# MFP_PCB_2layer_v2.net
KiCad netlist of a schematic drawn in EAGLE
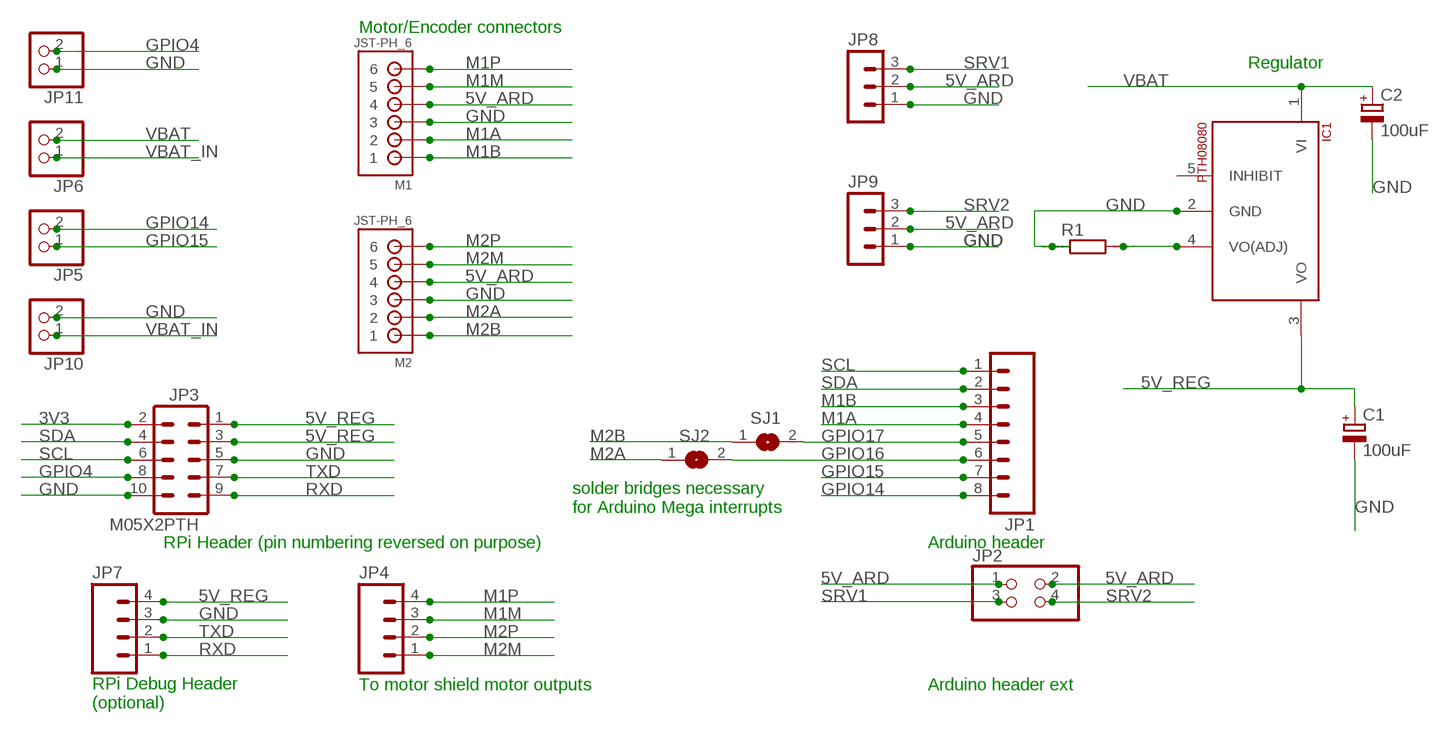
[diagram p0: schematic, sheet 1]

(export (version "E")
  (design (tool "Eeschema 10.0.6"))
  (components
    (comp (ref "C1")
      (value "100uF")
      (footprint "eagle-import:150CLZ-0810")
      (libsource (lib "eagle-import") (part "CPOL-EU150CLZ-0810"))
    )
    (comp (ref "C2")
      (value "100uF")
      (footprint "eagle-import:150CLZ-0810")
      (libsource (lib "eagle-import") (part "CPOL-EU150CLZ-0810"))
    )
    (comp (ref "IC1")
      (value "PTH08080")
      (footprint "eagle-import:PTH08080")
      (libsource (lib "eagle-import") (part "PTH08080"))
    )
    (comp (ref "JP1")
      (value "M08LONGPADS")
      (footprint "eagle-import:1X08_LONGPADS")
      (libsource (lib "eagle-import") (part "M08LONGPADS"))
    )
    (comp (ref "JP2")
      (value "PINHD-2X2")
      (footprint "eagle-import:2X02")
      (libsource (lib "eagle-import") (part "PINHD-2X2"))
    )
    (comp (ref "JP3")
      (value "M05X2PTH")
      (footprint "eagle-import:AVR_ICSP")
      (libsource (lib "eagle-import") (part "M05X2PTH"))
    )
    (comp (ref "JP4")
      (value "M04PTH")
      (footprint "eagle-import:1X04")
      (libsource (lib "eagle-import") (part "M04PTH"))
    )
    (comp (ref "JP5")
      (value "PINHD-1X2")
      (footprint "eagle-import:1X02")
      (libsource (lib "eagle-import") (part "PINHD-1X2"))
    )
    (comp (ref "JP6")
      (value "PINHD-1X2")
      (footprint "eagle-import:1X02")
      (libsource (lib "eagle-import") (part "PINHD-1X2"))
    )
    (comp (ref "JP7")
      (value "M04PTH")
      (footprint "eagle-import:1X04")
      (libsource (lib "eagle-import") (part "M04PTH"))
    )
    (comp (ref "JP8")
      (value "MA03-1")
      (footprint "eagle-import:MA03-1")
      (libsource (lib "eagle-import") (part "MA03-1"))
    )
    (comp (ref "JP9")
      (value "MA03-1")
      (footprint "eagle-import:MA03-1")
      (libsource (lib "eagle-import") (part "MA03-1"))
    )
    (comp (ref "JP10")
      (value "PINHD-1X2")
      (footprint "eagle-import:1X02")
      (libsource (lib "eagle-import") (part "PINHD-1X2"))
    )
    (comp (ref "JP11")
      (value "PINHD-1X2")
      (footprint "eagle-import:1X02")
      (libsource (lib "eagle-import") (part "PINHD-1X2"))
    )
    (comp (ref "M1")
      (value "JST-PH_6")
      (footprint "eagle-import:JST_B6B-PH_HEADER")
      (libsource (lib "eagle-import") (part "JST-PH_6"))
    )
    (comp (ref "M2")
      (value "JST-PH_6")
      (footprint "eagle-import:JST_B6B-PH_HEADER")
      (libsource (lib "eagle-import") (part "JST-PH_6"))
    )
    (comp (ref "R1")
      (value "R0204/7")
      (footprint "eagle-import:0204_7")
      (libsource (lib "eagle-import") (part "R0204/7"))
    )
    (comp (ref "SJ1") (value "SJ") (footprint "eagle-import:SJ") (libsource (lib "eagle-import") (part "SJ")))
    (comp (ref "SJ2") (value "SJ") (footprint "eagle-import:SJ") (libsource (lib "eagle-import") (part "SJ")))
  )
  (nets
    (net (code "1") (name "/3V3") (class "Default")
      (node (ref "JP3") (pin "2") (pinfunction "2_2") (pintype "passive"))
    )
    (net (code "2") (name "/5V_ARD") (class "Default")
      (node (ref "JP2") (pin "1") (pinfunction "1_1") (pintype "passive"))
      (node (ref "JP2") (pin "2") (pinfunction "2_2") (pintype "passive"))
      (node (ref "JP8") (pin "2") (pinfunction "2_2") (pintype "passive"))
      (node (ref "JP9") (pin "2") (pinfunction "2_2") (pintype "passive"))
      (node (ref "M1") (pin "P4") (pinfunction "4_P4") (pintype "bidirectional"))
      (node (ref "M2") (pin "P4") (pinfunction "4_P4") (pintype "bidirectional"))
    )
    (net (code "3") (name "/5V_REG") (class "Default")
      (node (ref "C1") (pin "+") (pinfunction "+_+") (pintype "passive"))
      (node (ref "IC1") (pin "3") (pinfunction "VO_3") (pintype "bidirectional"))
      (node (ref "JP3") (pin "1") (pinfunction "1_1") (pintype "passive"))
      (node (ref "JP3") (pin "3") (pinfunction "3_3") (pintype "passive"))
      (node (ref "JP7") (pin "4") (pinfunction "4_4") (pintype "passive"))
    )
    (net (code "4") (name "/GND") (class "Default")
      (node (ref "C1") (pin "-") (pinfunction "-_-") (pintype "passive"))
      (node (ref "C2") (pin "-") (pinfunction "-_-") (pintype "passive"))
      (node (ref "IC1") (pin "2") (pinfunction "GND_2") (pintype "bidirectional"))
      (node (ref "JP10") (pin "2") (pinfunction "2_2") (pintype "passive"))
      (node (ref "JP11") (pin "1") (pinfunction "1_1") (pintype "passive"))
      (node (ref "JP3") (pin "10") (pinfunction "10_10") (pintype "passive"))
      (node (ref "JP3") (pin "5") (pinfunction "5_5") (pintype "passive"))
      (node (ref "JP7") (pin "3") (pinfunction "3_3") (pintype "passive"))
      (node (ref "JP8") (pin "1") (pinfunction "1_1") (pintype "passive"))
      (node (ref "JP9") (pin "1") (pinfunction "1_1") (pintype "passive"))
      (node (ref "M1") (pin "P3") (pinfunction "3_P3") (pintype "bidirectional"))
      (node (ref "M2") (pin "P3") (pinfunction "3_P3") (pintype "bidirectional"))
      (node (ref "R1") (pin "1") (pinfunction "1_1") (pintype "passive"))
    )
    (net (code "5") (name "/GPIO4") (class "Default")
      (node (ref "JP11") (pin "2") (pinfunction "2_2") (pintype "passive"))
      (node (ref "JP3") (pin "8") (pinfunction "8_8") (pintype "passive"))
    )
    (net (code "6") (name "/GPIO14") (class "Default")
      (node (ref "JP1") (pin "8") (pinfunction "8_8") (pintype "passive"))
      (node (ref "JP5") (pin "2") (pinfunction "2_2") (pintype "passive"))
    )
    (net (code "7") (name "/GPIO15") (class "Default")
      (node (ref "JP1") (pin "7") (pinfunction "7_7") (pintype "passive"))
      (node (ref "JP5") (pin "1") (pinfunction "1_1") (pintype "passive"))
    )
    (net (code "8") (name "/GPIO16") (class "Default")
      (node (ref "JP1") (pin "6") (pinfunction "6_6") (pintype "passive"))
      (node (ref "SJ2") (pin "2") (pinfunction "2_2") (pintype "passive"))
    )
    (net (code "9") (name "/GPIO17") (class "Default")
      (node (ref "JP1") (pin "5") (pinfunction "5_5") (pintype "passive"))
      (node (ref "SJ1") (pin "2") (pinfunction "2_2") (pintype "passive"))
    )
    (net (code "10") (name "/M1A") (class "Default")
      (node (ref "JP1") (pin "4") (pinfunction "4_4") (pintype "passive"))
      (node (ref "M1") (pin "P2") (pinfunction "2_P2") (pintype "bidirectional"))
    )
    (net (code "11") (name "/M1B") (class "Default")
      (node (ref "JP1") (pin "3") (pinfunction "3_3") (pintype "passive"))
      (node (ref "M1") (pin "P1") (pinfunction "1_P1") (pintype "bidirectional"))
    )
    (net (code "12") (name "/M1M") (class "Default")
      (node (ref "JP4") (pin "3") (pinfunction "3_3") (pintype "passive"))
      (node (ref "M1") (pin "P5") (pinfunction "5_P5") (pintype "bidirectional"))
    )
    (net (code "13") (name "/M1P") (class "Default")
      (node (ref "JP4") (pin "4") (pinfunction "4_4") (pintype "passive"))
      (node (ref "M1") (pin "P6") (pinfunction "6_P6") (pintype "bidirectional"))
    )
    (net (code "14") (name "/M2A") (class "Default")
      (node (ref "M2") (pin "P2") (pinfunction "2_P2") (pintype "bidirectional"))
      (node (ref "SJ2") (pin "1") (pinfunction "1_1") (pintype "passive"))
    )
    (net (code "15") (name "/M2B") (class "Default")
      (node (ref "M2") (pin "P1") (pinfunction "1_P1") (pintype "bidirectional"))
      (node (ref "SJ1") (pin "1") (pinfunction "1_1") (pintype "passive"))
    )
    (net (code "16") (name "/M2M") (class "Default")
      (node (ref "JP4") (pin "1") (pinfunction "1_1") (pintype "passive"))
      (node (ref "M2") (pin "P5") (pinfunction "5_P5") (pintype "bidirectional"))
    )
    (net (code "17") (name "/M2P") (class "Default")
      (node (ref "JP4") (pin "2") (pinfunction "2_2") (pintype "passive"))
      (node (ref "M2") (pin "P6") (pinfunction "6_P6") (pintype "bidirectional"))
    )
    (net (code "18") (name "/RXD") (class "Default")
      (node (ref "JP3") (pin "9") (pinfunction "9_9") (pintype "passive"))
      (node (ref "JP7") (pin "1") (pinfunction "1_1") (pintype "passive"))
    )
    (net (code "19") (name "/SCL") (class "Default")
      (node (ref "JP1") (pin "1") (pinfunction "1_1") (pintype "passive"))
      (node (ref "JP3") (pin "6") (pinfunction "6_6") (pintype "passive"))
    )
    (net (code "20") (name "/SDA") (class "Default")
      (node (ref "JP1") (pin "2") (pinfunction "2_2") (pintype "passive"))
      (node (ref "JP3") (pin "4") (pinfunction "4_4") (pintype "passive"))
    )
    (net (code "21") (name "/SRV1") (class "Default")
      (node (ref "JP2") (pin "3") (pinfunction "3_3") (pintype "passive"))
      (node (ref "JP8") (pin "3") (pinfunction "3_3") (pintype "passive"))
    )
    (net (code "22") (name "/SRV2") (class "Default")
      (node (ref "JP2") (pin "4") (pinfunction "4_4") (pintype "passive"))
      (node (ref "JP9") (pin "3") (pinfunction "3_3") (pintype "passive"))
    )
    (net (code "23") (name "/TXD") (class "Default")
      (node (ref "JP3") (pin "7") (pinfunction "7_7") (pintype "passive"))
      (node (ref "JP7") (pin "2") (pinfunction "2_2") (pintype "passive"))
    )
    (net (code "24") (name "/VBAT") (class "Default")
      (node (ref "C2") (pin "+") (pinfunction "+_+") (pintype "passive"))
      (node (ref "IC1") (pin "1") (pinfunction "VI_1") (pintype "bidirectional"))
      (node (ref "JP6") (pin "2") (pinfunction "2_2") (pintype "passive"))
    )
    (net (code "25") (name "/VBAT_IN") (class "Default")
      (node (ref "JP10") (pin "1") (pinfunction "1_1") (pintype "passive"))
      (node (ref "JP6") (pin "1") (pinfunction "1_1") (pintype "passive"))
    )
    (net (code "26") (name "Net-(IC1-VO(ADJ))") (class "Default")
      (node (ref "IC1") (pin "4") (pinfunction "VO(ADJ)_4") (pintype "bidirectional"))
      (node (ref "R1") (pin "2") (pinfunction "2_2") (pintype "passive"))
    )
    (net (code "27") (name "unconnected-(IC1-INHIBIT-Pad5)") (class "Default")
      (node (ref "IC1") (pin "5") (pinfunction "INHIBIT_5") (pintype "bidirectional"))
    )
  )
)
